# PISO.net
KiCad netlist of a schematic drawn in Altium Designer
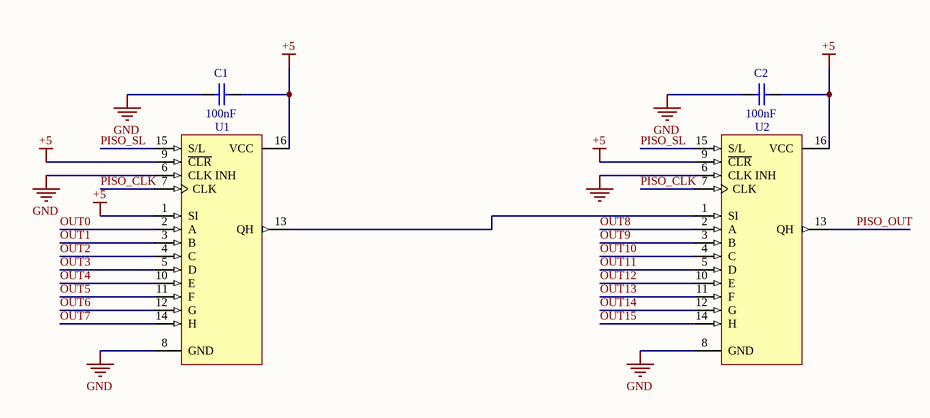
[diagram p0: PISO.SchDoc]

(export (version "E")
  (design (tool "Eeschema 10.0.6"))
  (components
    (comp (ref "C1")
      (value "100nF")
      (footprint "C1206")
      (fields
        (field (name "Comment") "http://www.tme.eu/pl/details/12061c104kat2a/kondensatory-mlcc-smd-1206/avx/")
        (field (name "PUBLISHER") "Altium Limited")
      )
      (libsource (lib "Miscellaneous Devices") (part "Cap"))
    )
    (comp (ref "C2")
      (value "100nF")
      (footprint "C1206")
      (fields
        (field (name "Comment") "http://www.tme.eu/pl/details/12061c104kat2a/kondensatory-mlcc-smd-1206/avx/")
        (field (name "PUBLISHER") "Altium Limited")
      )
      (libsource (lib "Miscellaneous Devices") (part "Cap"))
    )
    (comp (ref "U1")
      (value "http://www.tme.eu/pl/details/sn74hc166d/rejestry-przesuwne/texas-instruments/")
      (footprint "D016_N")
      (description "SN74HC166")
      (fields (field (name "PUBLISHER") "Altium Limited"))
      (libsource (lib "TI Logic Register") (part "SN74HC166D"))
    )
    (comp (ref "U2")
      (value "http://www.tme.eu/pl/details/sn74hc166d/rejestry-przesuwne/texas-instruments/")
      (footprint "D016_N")
      (description "SN74HC166")
      (fields (field (name "PUBLISHER") "Altium Limited"))
      (libsource (lib "TI Logic Register") (part "SN74HC166D"))
    )
  )
  (nets
    (net (code "1") (name "+5") (class "Default")
      (node (ref "C1") (pin "2") (pinfunction "2_2") (pintype "passive"))
      (node (ref "C2") (pin "2") (pinfunction "2_2") (pintype "passive"))
      (node (ref "U1") (pin "1") (pinfunction "SI_1") (pintype "input"))
      (node (ref "U1") (pin "16") (pinfunction "VCC_16") (pintype "power_in"))
      (node (ref "U1") (pin "9") (pinfunction "~{CLR}_9") (pintype "input"))
      (node (ref "U2") (pin "16") (pinfunction "VCC_16") (pintype "power_in"))
      (node (ref "U2") (pin "9") (pinfunction "~{CLR}_9") (pintype "input"))
    )
    (net (code "2") (name "/OUT0") (class "Default")
      (node (ref "U1") (pin "2") (pinfunction "A_2") (pintype "input"))
    )
    (net (code "3") (name "/OUT1") (class "Default")
      (node (ref "U1") (pin "3") (pinfunction "B_3") (pintype "input"))
    )
    (net (code "4") (name "/OUT2") (class "Default")
      (node (ref "U1") (pin "4") (pinfunction "C_4") (pintype "input"))
    )
    (net (code "5") (name "/OUT3") (class "Default")
      (node (ref "U1") (pin "5") (pinfunction "D_5") (pintype "input"))
    )
    (net (code "6") (name "/OUT4") (class "Default")
      (node (ref "U1") (pin "10") (pinfunction "E_10") (pintype "input"))
    )
    (net (code "7") (name "/OUT5") (class "Default")
      (node (ref "U1") (pin "11") (pinfunction "F_11") (pintype "input"))
    )
    (net (code "8") (name "/OUT6") (class "Default")
      (node (ref "U1") (pin "12") (pinfunction "G_12") (pintype "input"))
    )
    (net (code "9") (name "/OUT7") (class "Default")
      (node (ref "U1") (pin "14") (pinfunction "H_14") (pintype "input"))
    )
    (net (code "10") (name "/OUT8") (class "Default")
      (node (ref "U2") (pin "2") (pinfunction "A_2") (pintype "input"))
    )
    (net (code "11") (name "/OUT9") (class "Default")
      (node (ref "U2") (pin "3") (pinfunction "B_3") (pintype "input"))
    )
    (net (code "12") (name "/OUT10") (class "Default")
      (node (ref "U2") (pin "4") (pinfunction "C_4") (pintype "input"))
    )
    (net (code "13") (name "/OUT11") (class "Default")
      (node (ref "U2") (pin "5") (pinfunction "D_5") (pintype "input"))
    )
    (net (code "14") (name "/OUT12") (class "Default")
      (node (ref "U2") (pin "10") (pinfunction "E_10") (pintype "input"))
    )
    (net (code "15") (name "/OUT13") (class "Default")
      (node (ref "U2") (pin "11") (pinfunction "F_11") (pintype "input"))
    )
    (net (code "16") (name "/OUT14") (class "Default")
      (node (ref "U2") (pin "12") (pinfunction "G_12") (pintype "input"))
    )
    (net (code "17") (name "/OUT15") (class "Default")
      (node (ref "U2") (pin "14") (pinfunction "H_14") (pintype "input"))
    )
    (net (code "18") (name "/PISO_CLK") (class "Default")
      (node (ref "U1") (pin "7") (pinfunction "CLK_7") (pintype "input"))
      (node (ref "U2") (pin "7") (pinfunction "CLK_7") (pintype "input"))
    )
    (net (code "19") (name "/PISO_OUT") (class "Default")
      (node (ref "U2") (pin "13") (pinfunction "QH_13") (pintype "output"))
    )
    (net (code "20") (name "/PISO_SL") (class "Default")
      (node (ref "U1") (pin "15") (pinfunction "S/L_15") (pintype "input"))
      (node (ref "U2") (pin "15") (pinfunction "S/L_15") (pintype "input"))
    )
    (net (code "21") (name "GND") (class "Default")
      (node (ref "C1") (pin "1") (pinfunction "1_1") (pintype "passive"))
      (node (ref "C2") (pin "1") (pinfunction "1_1") (pintype "passive"))
      (node (ref "U1") (pin "6") (pinfunction "CLK_INH_6") (pintype "input"))
      (node (ref "U1") (pin "8") (pinfunction "GND_8") (pintype "power_in"))
      (node (ref "U2") (pin "6") (pinfunction "CLK_INH_6") (pintype "input"))
      (node (ref "U2") (pin "8") (pinfunction "GND_8") (pintype "power_in"))
    )
    (net (code "22") (name "Net-(U1-QH)") (class "Default")
      (node (ref "U1") (pin "13") (pinfunction "QH_13") (pintype "output"))
      (node (ref "U2") (pin "1") (pinfunction "SI_1") (pintype "input"))
    )
  )
)
